# New_Project.net
KiCad netlist of a schematic drawn in EasyEDA
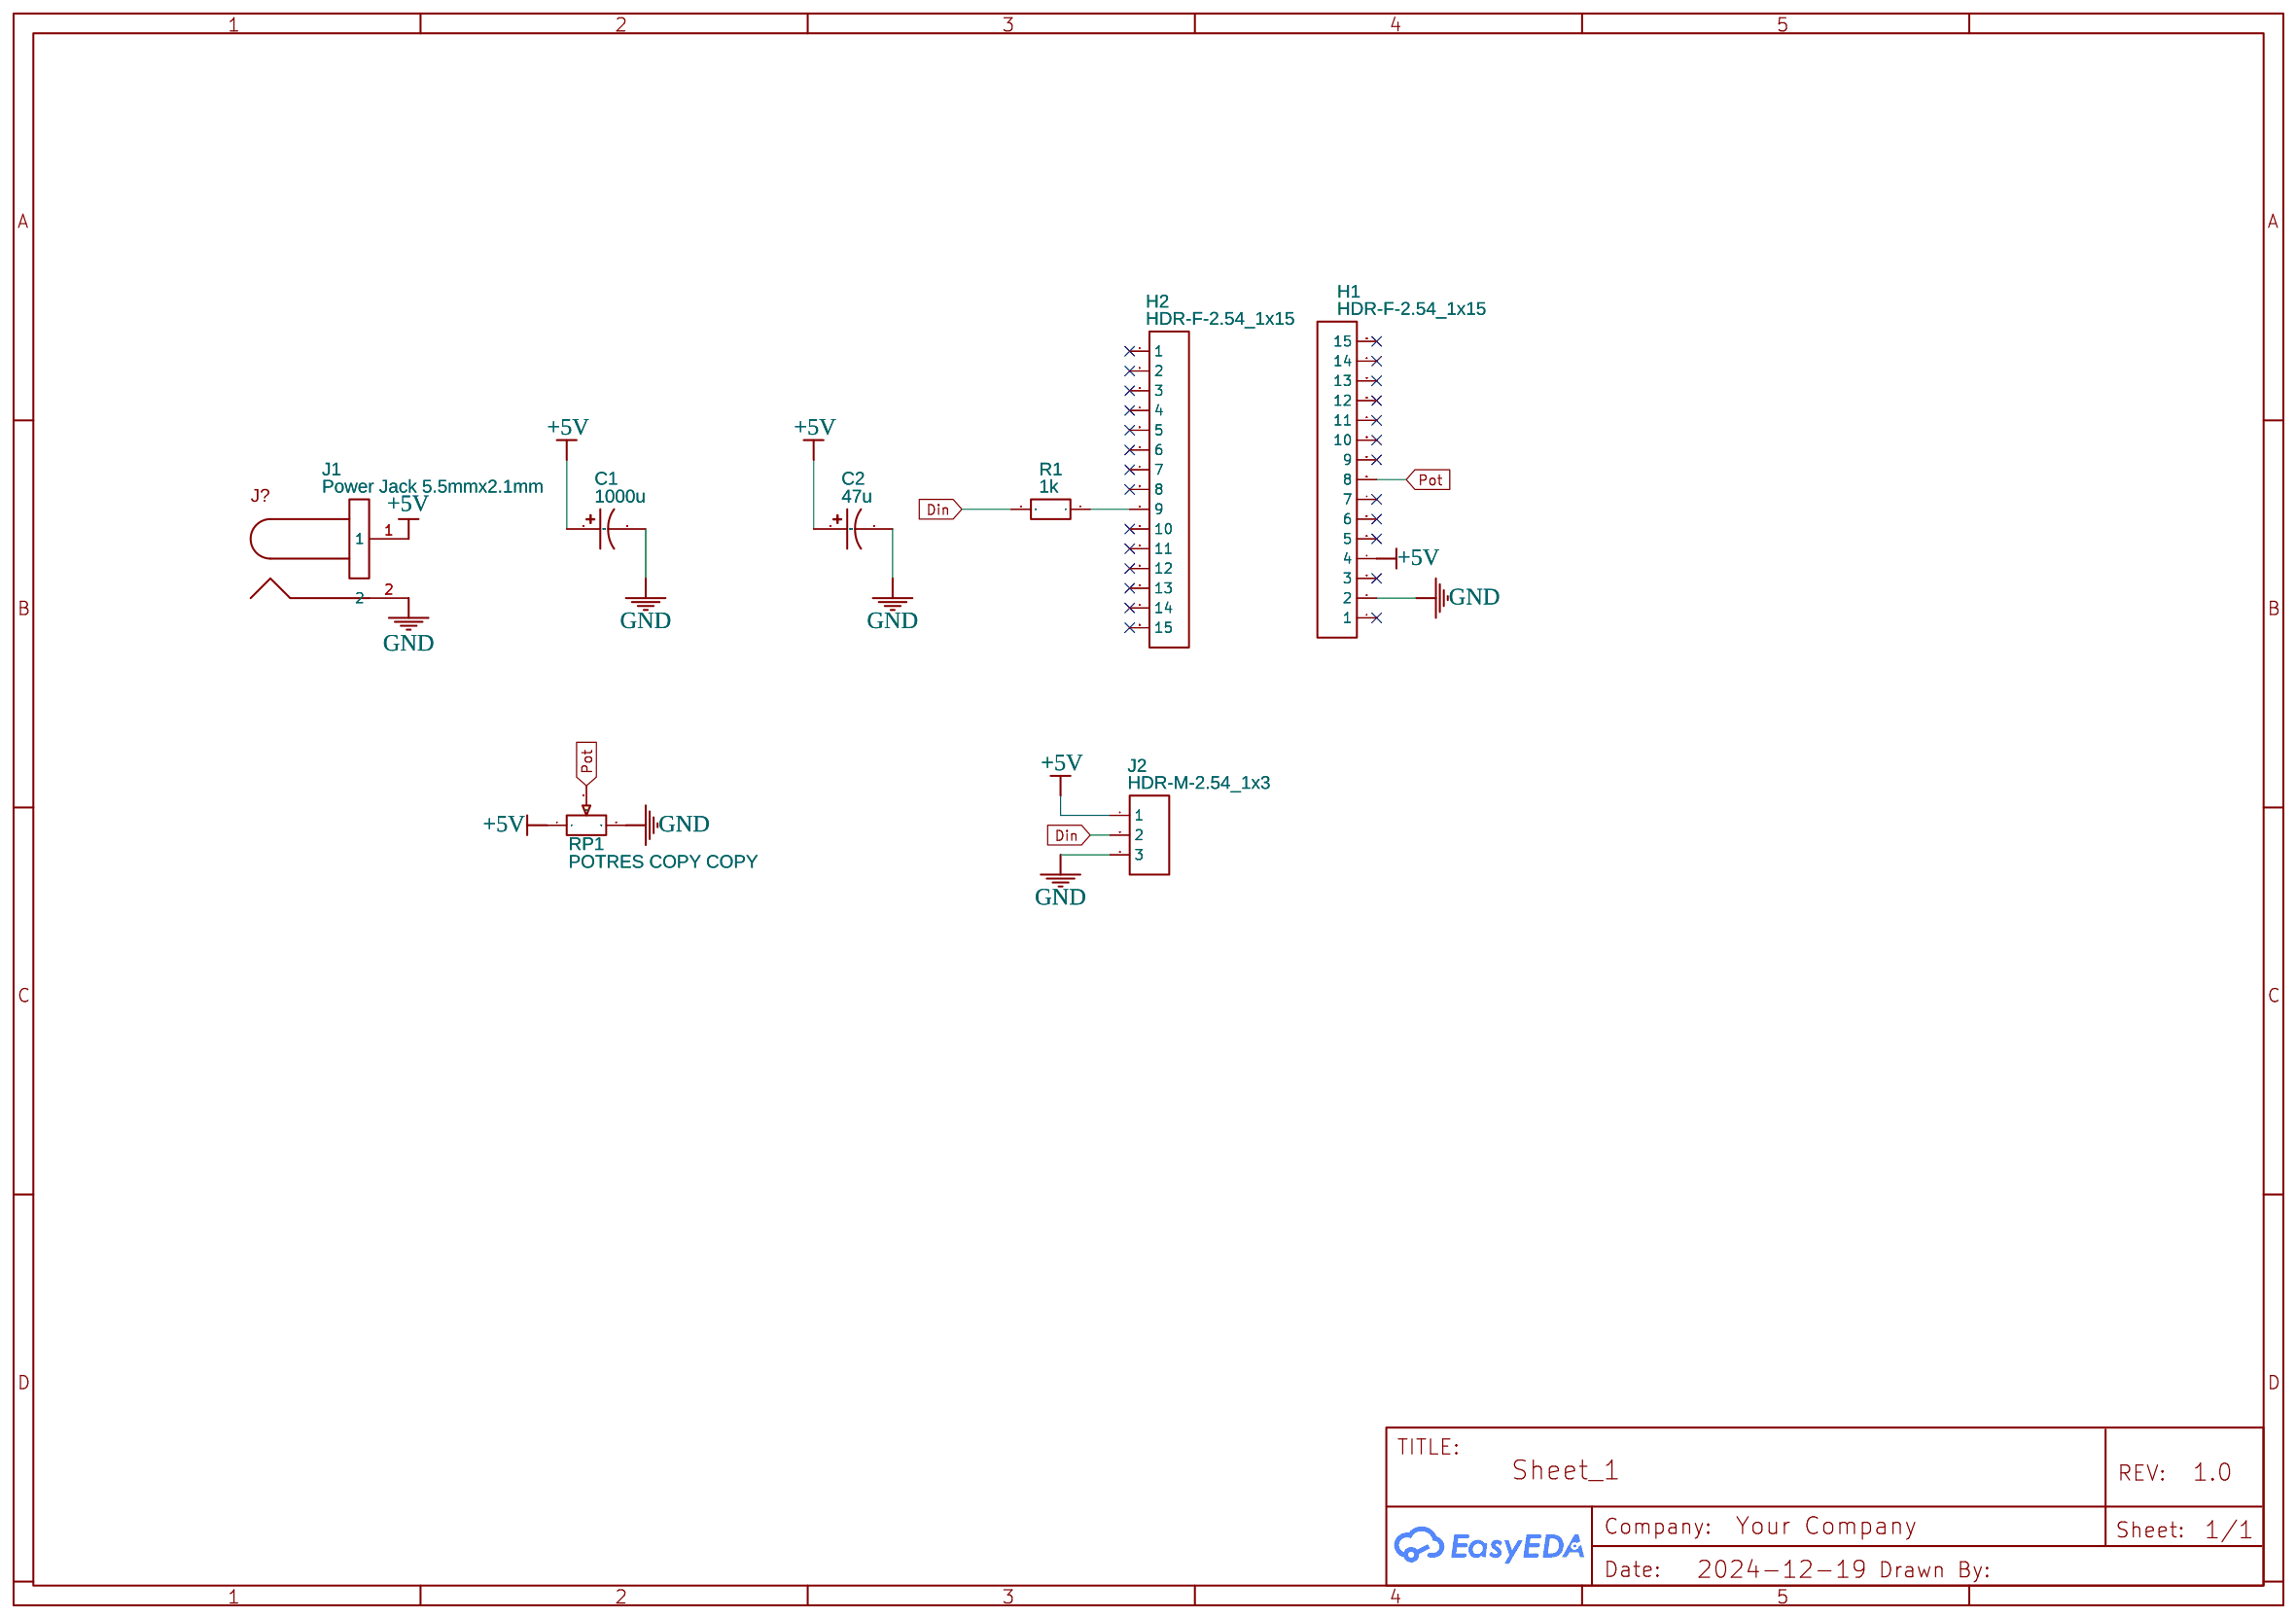
[diagram p0: schematic sheet]

(export (version "E")
  (design (tool "Eeschema 10.0.6"))
  (components
    (comp (ref "C1") (value "1000u") (libsource (lib "") (part "CE_TH_D4.0×F1.5_US")))
    (comp (ref "C2") (value "47u") (libsource (lib "") (part "CE_TH_D4.0×F1.5_US")))
    (comp (ref "H1") (value "HDR-F-2.54_1x15") (libsource (lib "") (part "HDR-F-2.54_1x15")))
    (comp (ref "H2") (value "HDR-F-2.54_1x15") (libsource (lib "") (part "HDR-F-2.54_1x15_1")))
    (comp (ref "J1")
      (value "Power Jack 5.5mmx2.1mm")
      (fields (field (name "Manufacturer Part") "54-00166") (field (name "Manufacturer") "Tensility"))
      (libsource (lib "") (part "Power Jack 5.5mmx2.1mm"))
    )
    (comp (ref "J2") (value "HDR-M-2.54_1x3") (libsource (lib "") (part "HDR-M-2.54_1x3")))
    (comp (ref "R1") (value "1k") (libsource (lib "") (part "R_AXIAL-0.4_EU")))
    (comp (ref "RP1") (value "POTRES COPY COPY") (libsource (lib "") (part "POTRES COPY COPY")))
  )
  (nets
    (net (code "1") (name "+5V") (class "Default")
      (node (ref "C1") (pin "1") (pinfunction "1_1") (pintype "unspecified"))
      (node (ref "C2") (pin "1") (pinfunction "1_1") (pintype "unspecified"))
      (node (ref "H1") (pin "4") (pinfunction "4_4") (pintype "unspecified"))
      (node (ref "J1") (pin "1") (pinfunction "1_1") (pintype "unspecified"))
      (node (ref "J2") (pin "1") (pinfunction "1_1") (pintype "input"))
      (node (ref "RP1") (pin "1") (pinfunction "1_1") (pintype "input"))
    )
    (net (code "2") (name "Din") (class "Default")
      (node (ref "J2") (pin "2") (pinfunction "2_2") (pintype "input"))
      (node (ref "R1") (pin "2") (pinfunction "2_2") (pintype "unspecified"))
    )
    (net (code "3") (name "GND") (class "Default")
      (node (ref "C1") (pin "2") (pinfunction "2_2") (pintype "unspecified"))
      (node (ref "C2") (pin "2") (pinfunction "2_2") (pintype "unspecified"))
      (node (ref "H1") (pin "2") (pinfunction "2_2") (pintype "unspecified"))
      (node (ref "J1") (pin "2") (pinfunction "2_2") (pintype "unspecified"))
      (node (ref "J2") (pin "3") (pinfunction "3_3") (pintype "input"))
      (node (ref "RP1") (pin "3") (pinfunction "3_3") (pintype "input"))
    )
    (net (code "4") (name "Net-(H2-Pad9)") (class "Default")
      (node (ref "H2") (pin "9") (pinfunction "9_9") (pintype "unspecified"))
      (node (ref "R1") (pin "1") (pinfunction "1_1") (pintype "unspecified"))
    )
    (net (code "5") (name "Pot") (class "Default")
      (node (ref "H1") (pin "8") (pinfunction "8_8") (pintype "unspecified"))
      (node (ref "RP1") (pin "2") (pinfunction "2_2") (pintype "input"))
    )
    (net (code "6") (name "unconnected-(H1-Pad1)") (class "Default")
      (node (ref "H1") (pin "1") (pinfunction "1_1") (pintype "unspecified+no_connect"))
    )
    (net (code "7") (name "unconnected-(H1-Pad3)") (class "Default")
      (node (ref "H1") (pin "3") (pinfunction "3_3") (pintype "unspecified+no_connect"))
    )
    (net (code "8") (name "unconnected-(H1-Pad5)") (class "Default")
      (node (ref "H1") (pin "5") (pinfunction "5_5") (pintype "unspecified+no_connect"))
    )
    (net (code "9") (name "unconnected-(H1-Pad6)") (class "Default")
      (node (ref "H1") (pin "6") (pinfunction "6_6") (pintype "unspecified+no_connect"))
    )
    (net (code "10") (name "unconnected-(H1-Pad7)") (class "Default")
      (node (ref "H1") (pin "7") (pinfunction "7_7") (pintype "unspecified+no_connect"))
    )
    (net (code "11") (name "unconnected-(H1-Pad9)") (class "Default")
      (node (ref "H1") (pin "9") (pinfunction "9_9") (pintype "unspecified+no_connect"))
    )
    (net (code "12") (name "unconnected-(H1-Pad10)") (class "Default")
      (node (ref "H1") (pin "10") (pinfunction "10_10") (pintype "unspecified+no_connect"))
    )
    (net (code "13") (name "unconnected-(H1-Pad11)") (class "Default")
      (node (ref "H1") (pin "11") (pinfunction "11_11") (pintype "unspecified+no_connect"))
    )
    (net (code "14") (name "unconnected-(H1-Pad12)") (class "Default")
      (node (ref "H1") (pin "12") (pinfunction "12_12") (pintype "unspecified+no_connect"))
    )
    (net (code "15") (name "unconnected-(H1-Pad13)") (class "Default")
      (node (ref "H1") (pin "13") (pinfunction "13_13") (pintype "unspecified+no_connect"))
    )
    (net (code "16") (name "unconnected-(H1-Pad14)") (class "Default")
      (node (ref "H1") (pin "14") (pinfunction "14_14") (pintype "unspecified+no_connect"))
    )
    (net (code "17") (name "unconnected-(H1-Pad15)") (class "Default")
      (node (ref "H1") (pin "15") (pinfunction "15_15") (pintype "unspecified+no_connect"))
    )
    (net (code "18") (name "unconnected-(H2-Pad1)") (class "Default")
      (node (ref "H2") (pin "1") (pinfunction "1_1") (pintype "unspecified+no_connect"))
    )
    (net (code "19") (name "unconnected-(H2-Pad2)") (class "Default")
      (node (ref "H2") (pin "2") (pinfunction "2_2") (pintype "unspecified+no_connect"))
    )
    (net (code "20") (name "unconnected-(H2-Pad3)") (class "Default")
      (node (ref "H2") (pin "3") (pinfunction "3_3") (pintype "unspecified+no_connect"))
    )
    (net (code "21") (name "unconnected-(H2-Pad4)") (class "Default")
      (node (ref "H2") (pin "4") (pinfunction "4_4") (pintype "unspecified+no_connect"))
    )
    (net (code "22") (name "unconnected-(H2-Pad5)") (class "Default")
      (node (ref "H2") (pin "5") (pinfunction "5_5") (pintype "unspecified+no_connect"))
    )
    (net (code "23") (name "unconnected-(H2-Pad6)") (class "Default")
      (node (ref "H2") (pin "6") (pinfunction "6_6") (pintype "unspecified+no_connect"))
    )
    (net (code "24") (name "unconnected-(H2-Pad7)") (class "Default")
      (node (ref "H2") (pin "7") (pinfunction "7_7") (pintype "unspecified+no_connect"))
    )
    (net (code "25") (name "unconnected-(H2-Pad8)") (class "Default")
      (node (ref "H2") (pin "8") (pinfunction "8_8") (pintype "unspecified+no_connect"))
    )
    (net (code "26") (name "unconnected-(H2-Pad10)") (class "Default")
      (node (ref "H2") (pin "10") (pinfunction "10_10") (pintype "unspecified+no_connect"))
    )
    (net (code "27") (name "unconnected-(H2-Pad11)") (class "Default")
      (node (ref "H2") (pin "11") (pinfunction "11_11") (pintype "unspecified+no_connect"))
    )
    (net (code "28") (name "unconnected-(H2-Pad12)") (class "Default")
      (node (ref "H2") (pin "12") (pinfunction "12_12") (pintype "unspecified+no_connect"))
    )
    (net (code "29") (name "unconnected-(H2-Pad13)") (class "Default")
      (node (ref "H2") (pin "13") (pinfunction "13_13") (pintype "unspecified+no_connect"))
    )
    (net (code "30") (name "unconnected-(H2-Pad14)") (class "Default")
      (node (ref "H2") (pin "14") (pinfunction "14_14") (pintype "unspecified+no_connect"))
    )
    (net (code "31") (name "unconnected-(H2-Pad15)") (class "Default")
      (node (ref "H2") (pin "15") (pinfunction "15_15") (pintype "unspecified+no_connect"))
    )
  )
)
